# VIBRO.net
KiCad netlist of a schematic drawn in Altium Designer
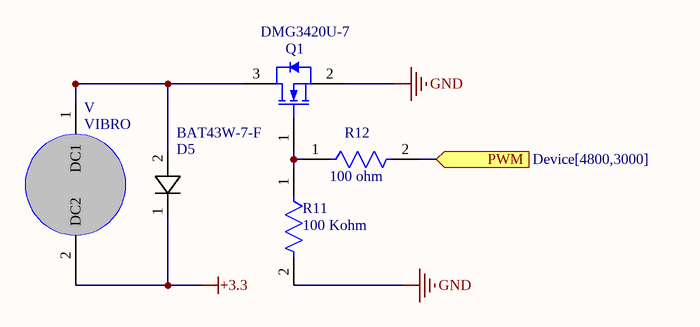
[diagram p0: VIBRO.SchDoc]

(export (version "E")
  (design (tool "Eeschema 10.0.6"))
  (components
    (comp (ref "D5")
      (value "BAT43W-7-F")
      (footprint "BAT43W-7-F")
      (libsource (lib "ReadyButNotListed") (part "BAT43W-7-F"))
    )
    (comp (ref "Q1")
      (value "DMG3420U-7")
      (footprint "DIOD-SOT23-3_B_V")
      (description "N-Channel Enhancement Mode MOSFET, 20 V, -55 to 150 degC, 3-Pin SOT23, RoHS, Tape and Reel")
      (fields (field (name "MANUFACTURER") "Diodes Inc"))
      (libsource (lib "Altium Content Vault") (part "NEMOS-GSD-3"))
    )
    (comp (ref "R11")
      (value "100 Kohm")
      (footprint "FP-RC1005-IPC_C")
      (description "Res Thick Film 0402 1.87kΩ 1% 0.063W ±100ppm/°C Molded SMD T/R")
      (fields (field (name "TOLERANCE") "1%"))
      (libsource (lib "Altium Content Vault") (part "1029c3af85768c4190bb7ad29bc67b5"))
    )
    (comp (ref "R12")
      (value "100 ohm")
      (footprint "FP-RC1005-IPC_C")
      (description "Res Thick Film 0402 1.87kΩ 1% 0.063W ±100ppm/°C Molded SMD T/R")
      (fields (field (name "TOLERANCE") "1%"))
      (libsource (lib "Altium Content Vault") (part "1029c3af85768c4190bb7ad29bc67b5"))
    )
    (comp (ref "V") (value "VIBRO") (footprint "VIBRO") (libsource (lib "Custom.") (part "VIBRO")))
  )
  (nets
    (net (code "1") (name "+3.3") (class "Default")
      (node (ref "D5") (pin "1") (pinfunction "1_1") (pintype "passive"))
      (node (ref "V") (pin "2") (pinfunction "DC2_2") (pintype "passive"))
    )
    (net (code "2") (name "/PWM") (class "Default")
      (node (ref "R12") (pin "2") (pinfunction "2_2") (pintype "passive"))
    )
    (net (code "3") (name "GND") (class "Default")
      (node (ref "Q1") (pin "2") (pinfunction "S_2") (pintype "passive"))
      (node (ref "R11") (pin "2") (pinfunction "2_2") (pintype "passive"))
    )
    (net (code "4") (name "Net-(Q1-D)") (class "Default")
      (node (ref "D5") (pin "2") (pinfunction "2_2") (pintype "passive"))
      (node (ref "Q1") (pin "3") (pinfunction "D_3") (pintype "passive"))
      (node (ref "V") (pin "1") (pinfunction "DC1_1") (pintype "passive"))
    )
    (net (code "5") (name "Net-(Q1-G)") (class "Default")
      (node (ref "Q1") (pin "1") (pinfunction "G_1") (pintype "passive"))
      (node (ref "R11") (pin "1") (pinfunction "1_1") (pintype "passive"))
      (node (ref "R12") (pin "1") (pinfunction "1_1") (pintype "passive"))
    )
  )
)
